# Rx.net
KiCad netlist of a schematic drawn in EAGLE
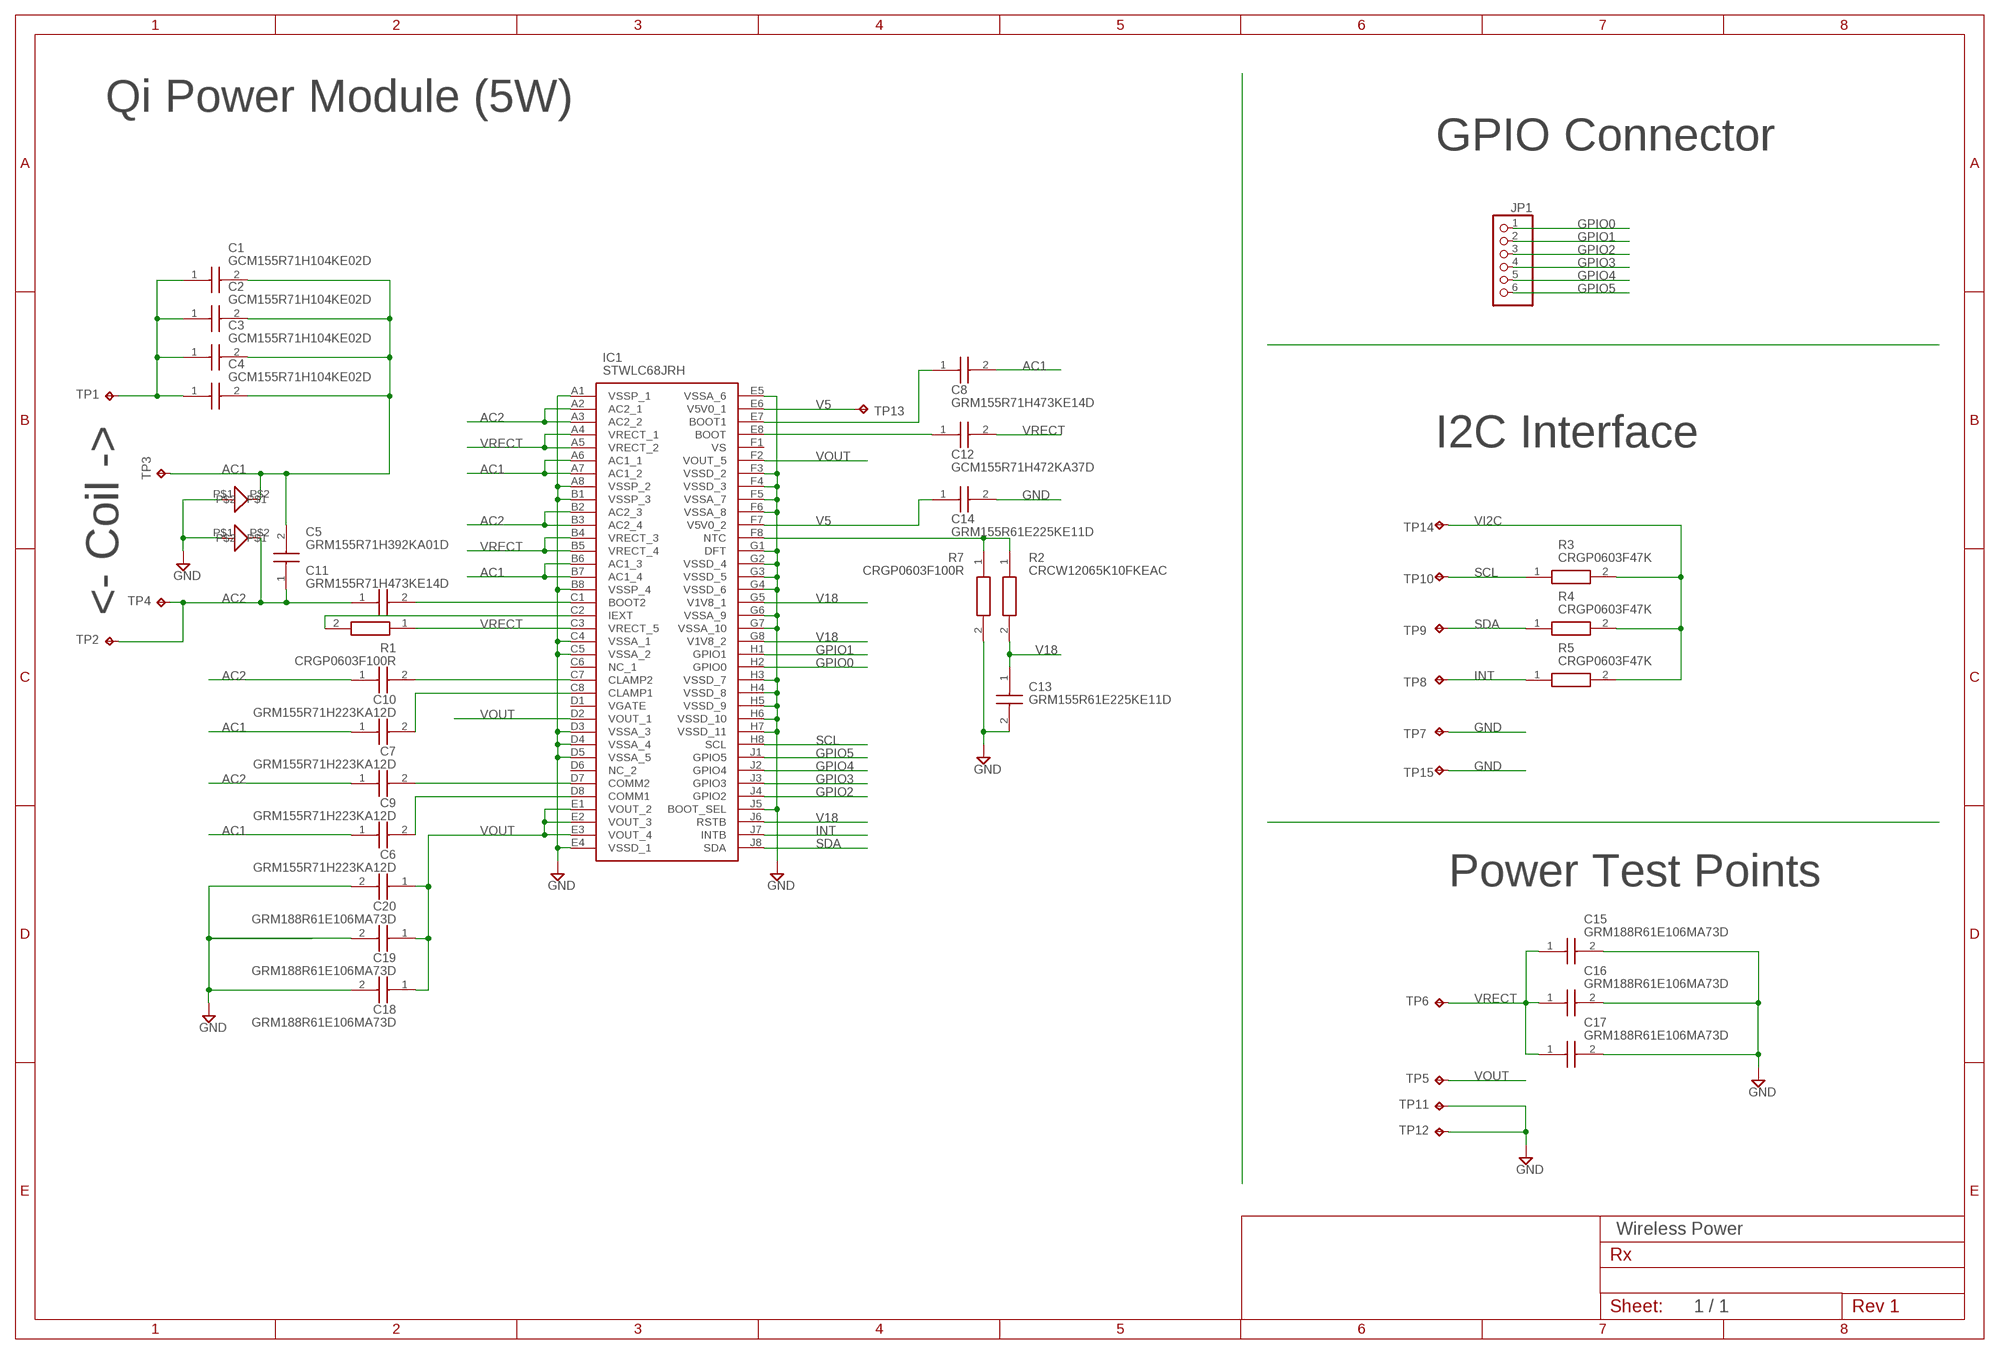
[diagram p0: schematic, sheet 1]

(export (version "E")
  (design (tool "Eeschema 10.0.6"))
  (components
    (comp (ref "C1")
      (value "GCM155R71H104KE02D")
      (footprint "eagle-import:CAPC1005X55N")
      (fields (field (name "MOUSER_PART_NUMBER") "81-GCM155R71H104KE2D"))
      (libsource (lib "eagle-import") (part "GCM155R71H104KE02D"))
    )
    (comp (ref "C2")
      (value "GCM155R71H104KE02D")
      (footprint "eagle-import:CAPC1005X55N")
      (fields (field (name "MOUSER_PART_NUMBER") "81-GCM155R71H104KE2D"))
      (libsource (lib "eagle-import") (part "GCM155R71H104KE02D"))
    )
    (comp (ref "C3")
      (value "GCM155R71H104KE02D")
      (footprint "eagle-import:CAPC1005X55N")
      (fields (field (name "MOUSER_PART_NUMBER") "81-GCM155R71H104KE2D"))
      (libsource (lib "eagle-import") (part "GCM155R71H104KE02D"))
    )
    (comp (ref "C4")
      (value "GCM155R71H104KE02D")
      (footprint "eagle-import:CAPC1005X55N")
      (fields (field (name "MOUSER_PART_NUMBER") "81-GCM155R71H104KE2D"))
      (libsource (lib "eagle-import") (part "GCM155R71H104KE02D"))
    )
    (comp (ref "C5")
      (value "GRM155R71H392KA01D")
      (footprint "eagle-import:CAPC1005X55N")
      (fields (field (name "MOUSER_PART_NUMBER") "81-GRM15R71H392KA01D"))
      (libsource (lib "eagle-import") (part "GRM155R71H392KA01D"))
    )
    (comp (ref "C6")
      (value "GRM155R71H223KA12D")
      (footprint "eagle-import:CAPC1005X55N")
      (fields (field (name "MOUSER_PART_NUMBER") "81-GRM155R71H223KA12"))
      (libsource (lib "eagle-import") (part "GRM155R71H223KA12D"))
    )
    (comp (ref "C7")
      (value "GRM155R71H223KA12D")
      (footprint "eagle-import:CAPC1005X55N")
      (fields (field (name "MOUSER_PART_NUMBER") "81-GRM155R71H223KA12"))
      (libsource (lib "eagle-import") (part "GRM155R71H223KA12D"))
    )
    (comp (ref "C8")
      (value "GRM155R71H473KE14D")
      (footprint "eagle-import:CAPC1005X55N")
      (fields (field (name "MOUSER_PART_NUMBER") "81-GRM155R71H473KE4D"))
      (libsource (lib "eagle-import") (part "GRM155R71H473KE14D"))
    )
    (comp (ref "C9")
      (value "GRM155R71H223KA12D")
      (footprint "eagle-import:CAPC1005X55N")
      (fields (field (name "MOUSER_PART_NUMBER") "81-GRM155R71H223KA12"))
      (libsource (lib "eagle-import") (part "GRM155R71H223KA12D"))
    )
    (comp (ref "C10")
      (value "GRM155R71H223KA12D")
      (footprint "eagle-import:CAPC1005X55N")
      (fields (field (name "MOUSER_PART_NUMBER") "81-GRM155R71H223KA12"))
      (libsource (lib "eagle-import") (part "GRM155R71H223KA12D"))
    )
    (comp (ref "C11")
      (value "GRM155R71H473KE14D")
      (footprint "eagle-import:CAPC1005X55N")
      (fields (field (name "MOUSER_PART_NUMBER") "81-GRM155R71H473KE4D"))
      (libsource (lib "eagle-import") (part "GRM155R71H473KE14D"))
    )
    (comp (ref "C12")
      (value "GCM155R71H472KA37D")
      (footprint "eagle-import:CAPC1005X55N")
      (fields (field (name "MOUSER_PART_NUMBER") "81-GCM155R71H472K37D"))
      (libsource (lib "eagle-import") (part "GCM155R71H472KA37D"))
    )
    (comp (ref "C13")
      (value "GRM155R61E225KE11D")
      (footprint "eagle-import:CAPC1005X55N")
      (fields (field (name "MOUSER_PART_NUMBER") "81-GRM155R61E225KE1D"))
      (libsource (lib "eagle-import") (part "GRM155R61E225KE11D"))
    )
    (comp (ref "C14")
      (value "GRM155R61E225KE11D")
      (footprint "eagle-import:CAPC1005X55N")
      (fields (field (name "MOUSER_PART_NUMBER") "81-GRM155R61E225KE1D"))
      (libsource (lib "eagle-import") (part "GRM155R61E225KE11D"))
    )
    (comp (ref "C15")
      (value "GRM188R61E106MA73D")
      (footprint "eagle-import:CAPC1608X90N")
      (fields (field (name "MOUSER_PART_NUMBER") "81-GRM188R61E106MA3D"))
      (libsource (lib "eagle-import") (part "GRM188R61E106MA73D"))
    )
    (comp (ref "C16")
      (value "GRM188R61E106MA73D")
      (footprint "eagle-import:CAPC1608X90N")
      (fields (field (name "MOUSER_PART_NUMBER") "81-GRM188R61E106MA3D"))
      (libsource (lib "eagle-import") (part "GRM188R61E106MA73D"))
    )
    (comp (ref "C17")
      (value "GRM188R61E106MA73D")
      (footprint "eagle-import:CAPC1608X90N")
      (fields (field (name "MOUSER_PART_NUMBER") "81-GRM188R61E106MA3D"))
      (libsource (lib "eagle-import") (part "GRM188R61E106MA73D"))
    )
    (comp (ref "C18")
      (value "GRM188R61E106MA73D")
      (footprint "eagle-import:CAPC1608X90N")
      (fields (field (name "MOUSER_PART_NUMBER") "81-GRM188R61E106MA3D"))
      (libsource (lib "eagle-import") (part "GRM188R61E106MA73D"))
    )
    (comp (ref "C19")
      (value "GRM188R61E106MA73D")
      (footprint "eagle-import:CAPC1608X90N")
      (fields (field (name "MOUSER_PART_NUMBER") "81-GRM188R61E106MA3D"))
      (libsource (lib "eagle-import") (part "GRM188R61E106MA73D"))
    )
    (comp (ref "C20")
      (value "GRM188R61E106MA73D")
      (footprint "eagle-import:CAPC1608X90N")
      (fields (field (name "MOUSER_PART_NUMBER") "81-GRM188R61E106MA3D"))
      (libsource (lib "eagle-import") (part "GRM188R61E106MA73D"))
    )
    (comp (ref "IC1")
      (value "STWLC68JRH")
      (footprint "eagle-import:BGA72C40P9X9_441X376X58")
      (fields (field (name "MOUSER_PART_NUMBER") "511-STWLC68JRH"))
      (libsource (lib "eagle-import") (part "STWLC68JRH"))
    )
    (comp (ref "JP1")
      (value "PINHD-1X6")
      (footprint "eagle-import:1X06")
      (libsource (lib "eagle-import") (part "PINHD-1X6"))
    )
    (comp (ref "R1")
      (value "CRGP0603F100R")
      (footprint "eagle-import:RESC1608X55N")
      (fields (field (name "MOUSER_PART_NUMBER") "279-CRGP0603F100R"))
      (libsource (lib "eagle-import") (part "CRGP0603F100R"))
    )
    (comp (ref "R2")
      (value "CRCW12065K10FKEAC")
      (footprint "eagle-import:RESC3216X60N")
      (fields (field (name "MOUSER_PART_NUMBER") "71-CRCW12065K10FKEAC"))
      (libsource (lib "eagle-import") (part "CRCW12065K10FKEAC"))
    )
    (comp (ref "R3")
      (value "CRGP0603F47K")
      (footprint "eagle-import:RESC1608X55N")
      (fields (field (name "MOUSER_PART_NUMBER") "279-CRGP0603F47K"))
      (libsource (lib "eagle-import") (part "CRGP0603F47K"))
    )
    (comp (ref "R4")
      (value "CRGP0603F47K")
      (footprint "eagle-import:RESC1608X55N")
      (fields (field (name "MOUSER_PART_NUMBER") "279-CRGP0603F47K"))
      (libsource (lib "eagle-import") (part "CRGP0603F47K"))
    )
    (comp (ref "R5")
      (value "CRGP0603F47K")
      (footprint "eagle-import:RESC1608X55N")
      (fields (field (name "MOUSER_PART_NUMBER") "279-CRGP0603F47K"))
      (libsource (lib "eagle-import") (part "CRGP0603F47K"))
    )
    (comp (ref "R7")
      (value "CRGP0603F100R")
      (footprint "eagle-import:RESC1608X55N")
      (fields (field (name "MOUSER_PART_NUMBER") "279-CRGP0603F100R"))
      (libsource (lib "eagle-import") (part "CRGP0603F100R"))
    )
    (comp (ref "TP1")
      (value "TPPAD1-13")
      (footprint "eagle-import:P1-13")
      (libsource (lib "eagle-import") (part "TPPAD1-13"))
    )
    (comp (ref "TP2")
      (value "TPPAD1-13")
      (footprint "eagle-import:P1-13")
      (libsource (lib "eagle-import") (part "TPPAD1-13"))
    )
    (comp (ref "TP3")
      (value "TPPAD1-13")
      (footprint "eagle-import:P1-13")
      (libsource (lib "eagle-import") (part "TPPAD1-13"))
    )
    (comp (ref "TP4")
      (value "TPPAD1-13")
      (footprint "eagle-import:P1-13")
      (libsource (lib "eagle-import") (part "TPPAD1-13"))
    )
    (comp (ref "TP5")
      (value "TPPAD1-13")
      (footprint "eagle-import:P1-13")
      (libsource (lib "eagle-import") (part "TPPAD1-13"))
    )
    (comp (ref "TP6")
      (value "TPPAD1-13")
      (footprint "eagle-import:P1-13")
      (libsource (lib "eagle-import") (part "TPPAD1-13"))
    )
    (comp (ref "TP7")
      (value "TPPAD1-13")
      (footprint "eagle-import:P1-13")
      (libsource (lib "eagle-import") (part "TPPAD1-13"))
    )
    (comp (ref "TP8")
      (value "TPPAD1-13")
      (footprint "eagle-import:P1-13")
      (libsource (lib "eagle-import") (part "TPPAD1-13"))
    )
    (comp (ref "TP9")
      (value "TPPAD1-13")
      (footprint "eagle-import:P1-13")
      (libsource (lib "eagle-import") (part "TPPAD1-13"))
    )
    (comp (ref "TP10")
      (value "TPPAD1-13")
      (footprint "eagle-import:P1-13")
      (libsource (lib "eagle-import") (part "TPPAD1-13"))
    )
    (comp (ref "TP11")
      (value "TPPAD1-13")
      (footprint "eagle-import:P1-13")
      (libsource (lib "eagle-import") (part "TPPAD1-13"))
    )
    (comp (ref "TP12")
      (value "TPPAD1-13")
      (footprint "eagle-import:P1-13")
      (libsource (lib "eagle-import") (part "TPPAD1-13"))
    )
    (comp (ref "TP13")
      (value "TPPAD1-13")
      (footprint "eagle-import:P1-13")
      (libsource (lib "eagle-import") (part "TPPAD1-13"))
    )
    (comp (ref "TP14")
      (value "TPPAD1-13")
      (footprint "eagle-import:P1-13")
      (libsource (lib "eagle-import") (part "TPPAD1-13"))
    )
    (comp (ref "TP15")
      (value "TPPAD1-13")
      (footprint "eagle-import:P1-13")
      (libsource (lib "eagle-import") (part "TPPAD1-13"))
    )
    (comp (ref "U$1")
      (value "SMAJ16A")
      (footprint "eagle-import:SMAJ16A")
      (libsource (lib "eagle-import") (part "SMAJ16A"))
    )
    (comp (ref "U$2")
      (value "SMAJ16A")
      (footprint "eagle-import:SMAJ16A")
      (libsource (lib "eagle-import") (part "SMAJ16A"))
    )
  )
  (nets
    (net (code "1") (name "/AC1") (class "Default")
      (node (ref "C1") (pin "2") (pinfunction "2_2") (pintype "bidirectional"))
      (node (ref "C2") (pin "2") (pinfunction "2_2") (pintype "bidirectional"))
      (node (ref "C3") (pin "2") (pinfunction "2_2") (pintype "bidirectional"))
      (node (ref "C4") (pin "2") (pinfunction "2_2") (pintype "bidirectional"))
      (node (ref "C5") (pin "2") (pinfunction "2_2") (pintype "bidirectional"))
      (node (ref "C6") (pin "1") (pinfunction "1_1") (pintype "bidirectional"))
      (node (ref "C7") (pin "1") (pinfunction "1_1") (pintype "bidirectional"))
      (node (ref "C8") (pin "2") (pinfunction "2_2") (pintype "bidirectional"))
      (node (ref "IC1") (pin "A6") (pinfunction "AC1_1_A6") (pintype "bidirectional"))
      (node (ref "IC1") (pin "A7") (pinfunction "AC1_2_A7") (pintype "bidirectional"))
      (node (ref "IC1") (pin "B6") (pinfunction "AC1_3_B6") (pintype "bidirectional"))
      (node (ref "IC1") (pin "B7") (pinfunction "AC1_4_B7") (pintype "bidirectional"))
      (node (ref "TP3") (pin "TP") (pinfunction "TP_TP") (pintype "input"))
      (node (ref "U$1") (pin "P$2") (pinfunction "P$2_P$2") (pintype "output"))
    )
    (net (code "2") (name "/AC2") (class "Default")
      (node (ref "C10") (pin "1") (pinfunction "1_1") (pintype "bidirectional"))
      (node (ref "C11") (pin "1") (pinfunction "1_1") (pintype "bidirectional"))
      (node (ref "C5") (pin "1") (pinfunction "1_1") (pintype "bidirectional"))
      (node (ref "C9") (pin "1") (pinfunction "1_1") (pintype "bidirectional"))
      (node (ref "IC1") (pin "A2") (pinfunction "AC2_1_A2") (pintype "bidirectional"))
      (node (ref "IC1") (pin "A3") (pinfunction "AC2_2_A3") (pintype "bidirectional"))
      (node (ref "IC1") (pin "B2") (pinfunction "AC2_3_B2") (pintype "bidirectional"))
      (node (ref "IC1") (pin "B3") (pinfunction "AC2_4_B3") (pintype "bidirectional"))
      (node (ref "TP2") (pin "TP") (pinfunction "TP_TP") (pintype "input"))
      (node (ref "TP4") (pin "TP") (pinfunction "TP_TP") (pintype "input"))
      (node (ref "U$2") (pin "P$2") (pinfunction "P$2_P$2") (pintype "output"))
    )
    (net (code "3") (name "/GPIO0") (class "Default")
      (node (ref "IC1") (pin "H2") (pinfunction "GPIO0_H2") (pintype "bidirectional"))
      (node (ref "JP1") (pin "1") (pinfunction "1_1") (pintype "passive"))
    )
    (net (code "4") (name "/GPIO1") (class "Default")
      (node (ref "IC1") (pin "H1") (pinfunction "GPIO1_H1") (pintype "bidirectional"))
      (node (ref "JP1") (pin "2") (pinfunction "2_2") (pintype "passive"))
    )
    (net (code "5") (name "/GPIO2") (class "Default")
      (node (ref "IC1") (pin "J4") (pinfunction "GPIO2_J4") (pintype "bidirectional"))
      (node (ref "JP1") (pin "3") (pinfunction "3_3") (pintype "passive"))
    )
    (net (code "6") (name "/GPIO3") (class "Default")
      (node (ref "IC1") (pin "J3") (pinfunction "GPIO3_J3") (pintype "bidirectional"))
      (node (ref "JP1") (pin "4") (pinfunction "4_4") (pintype "passive"))
    )
    (net (code "7") (name "/GPIO4") (class "Default")
      (node (ref "IC1") (pin "J2") (pinfunction "GPIO4_J2") (pintype "bidirectional"))
      (node (ref "JP1") (pin "5") (pinfunction "5_5") (pintype "passive"))
    )
    (net (code "8") (name "/GPIO5") (class "Default")
      (node (ref "IC1") (pin "J1") (pinfunction "GPIO5_J1") (pintype "bidirectional"))
      (node (ref "JP1") (pin "6") (pinfunction "6_6") (pintype "passive"))
    )
    (net (code "9") (name "/INT") (class "Default")
      (node (ref "IC1") (pin "J7") (pinfunction "INTB_J7") (pintype "bidirectional"))
      (node (ref "R5") (pin "1") (pinfunction "1_1") (pintype "bidirectional"))
      (node (ref "TP8") (pin "TP") (pinfunction "TP_TP") (pintype "input"))
    )
    (net (code "11") (name "/SCL") (class "Default")
      (node (ref "IC1") (pin "H8") (pinfunction "SCL_H8") (pintype "bidirectional"))
      (node (ref "R3") (pin "1") (pinfunction "1_1") (pintype "bidirectional"))
      (node (ref "TP10") (pin "TP") (pinfunction "TP_TP") (pintype "input"))
    )
    (net (code "12") (name "/SDA") (class "Default")
      (node (ref "IC1") (pin "J8") (pinfunction "SDA_J8") (pintype "bidirectional"))
      (node (ref "R4") (pin "1") (pinfunction "1_1") (pintype "bidirectional"))
      (node (ref "TP9") (pin "TP") (pinfunction "TP_TP") (pintype "input"))
    )
    (net (code "13") (name "/V5") (class "Default")
      (node (ref "C14") (pin "1") (pinfunction "1_1") (pintype "bidirectional"))
      (node (ref "IC1") (pin "E6") (pinfunction "V5V0_1_E6") (pintype "bidirectional"))
      (node (ref "IC1") (pin "F7") (pinfunction "V5V0_2_F7") (pintype "bidirectional"))
      (node (ref "TP13") (pin "TP") (pinfunction "TP_TP") (pintype "input"))
    )
    (net (code "14") (name "/V18") (class "Default")
      (node (ref "C13") (pin "1") (pinfunction "1_1") (pintype "bidirectional"))
      (node (ref "IC1") (pin "G5") (pinfunction "V1V8_1_G5") (pintype "bidirectional"))
      (node (ref "IC1") (pin "G8") (pinfunction "V1V8_2_G8") (pintype "bidirectional"))
      (node (ref "IC1") (pin "J6") (pinfunction "RSTB_J6") (pintype "bidirectional"))
      (node (ref "R2") (pin "2") (pinfunction "2_2") (pintype "bidirectional"))
    )
    (net (code "15") (name "/VI2C") (class "Default")
      (node (ref "R3") (pin "2") (pinfunction "2_2") (pintype "bidirectional"))
      (node (ref "R4") (pin "2") (pinfunction "2_2") (pintype "bidirectional"))
      (node (ref "R5") (pin "2") (pinfunction "2_2") (pintype "bidirectional"))
      (node (ref "TP14") (pin "TP") (pinfunction "TP_TP") (pintype "input"))
    )
    (net (code "16") (name "/VOUT") (class "Default")
      (node (ref "C18") (pin "1") (pinfunction "1_1") (pintype "bidirectional"))
      (node (ref "C19") (pin "1") (pinfunction "1_1") (pintype "bidirectional"))
      (node (ref "C20") (pin "1") (pinfunction "1_1") (pintype "bidirectional"))
      (node (ref "IC1") (pin "D2") (pinfunction "VOUT_1_D2") (pintype "bidirectional"))
      (node (ref "IC1") (pin "E1") (pinfunction "VOUT_2_E1") (pintype "bidirectional"))
      (node (ref "IC1") (pin "E2") (pinfunction "VOUT_3_E2") (pintype "bidirectional"))
      (node (ref "IC1") (pin "E3") (pinfunction "VOUT_4_E3") (pintype "bidirectional"))
      (node (ref "IC1") (pin "F2") (pinfunction "VOUT_5_F2") (pintype "bidirectional"))
      (node (ref "TP5") (pin "TP") (pinfunction "TP_TP") (pintype "input"))
    )
    (net (code "17") (name "/VRECT") (class "Default")
      (node (ref "C12") (pin "2") (pinfunction "2_2") (pintype "bidirectional"))
      (node (ref "C15") (pin "1") (pinfunction "1_1") (pintype "bidirectional"))
      (node (ref "C16") (pin "1") (pinfunction "1_1") (pintype "bidirectional"))
      (node (ref "C17") (pin "1") (pinfunction "1_1") (pintype "bidirectional"))
      (node (ref "IC1") (pin "A4") (pinfunction "VRECT_1_A4") (pintype "bidirectional"))
      (node (ref "IC1") (pin "A5") (pinfunction "VRECT_2_A5") (pintype "bidirectional"))
      (node (ref "IC1") (pin "B4") (pinfunction "VRECT_3_B4") (pintype "bidirectional"))
      (node (ref "IC1") (pin "B5") (pinfunction "VRECT_4_B5") (pintype "bidirectional"))
      (node (ref "IC1") (pin "C3") (pinfunction "VRECT_5_C3") (pintype "bidirectional"))
      (node (ref "R1") (pin "1") (pinfunction "1_1") (pintype "bidirectional"))
      (node (ref "TP6") (pin "TP") (pinfunction "TP_TP") (pintype "input"))
    )
    (net (code "18") (name "GND") (class "Default")
      (node (ref "C13") (pin "2") (pinfunction "2_2") (pintype "bidirectional"))
      (node (ref "C14") (pin "2") (pinfunction "2_2") (pintype "bidirectional"))
      (node (ref "C15") (pin "2") (pinfunction "2_2") (pintype "bidirectional"))
      (node (ref "C16") (pin "2") (pinfunction "2_2") (pintype "bidirectional"))
      (node (ref "C17") (pin "2") (pinfunction "2_2") (pintype "bidirectional"))
      (node (ref "C18") (pin "2") (pinfunction "2_2") (pintype "bidirectional"))
      (node (ref "C19") (pin "2") (pinfunction "2_2") (pintype "bidirectional"))
      (node (ref "C20") (pin "2") (pinfunction "2_2") (pintype "bidirectional"))
      (node (ref "IC1") (pin "A1") (pinfunction "VSSP_1_A1") (pintype "bidirectional"))
      (node (ref "IC1") (pin "A8") (pinfunction "VSSP_2_A8") (pintype "bidirectional"))
      (node (ref "IC1") (pin "B1") (pinfunction "VSSP_3_B1") (pintype "bidirectional"))
      (node (ref "IC1") (pin "B8") (pinfunction "VSSP_4_B8") (pintype "bidirectional"))
      (node (ref "IC1") (pin "C4") (pinfunction "VSSA_1_C4") (pintype "bidirectional"))
      (node (ref "IC1") (pin "C5") (pinfunction "VSSA_2_C5") (pintype "bidirectional"))
      (node (ref "IC1") (pin "D3") (pinfunction "VSSA_3_D3") (pintype "bidirectional"))
      (node (ref "IC1") (pin "D4") (pinfunction "VSSA_4_D4") (pintype "bidirectional"))
      (node (ref "IC1") (pin "D5") (pinfunction "VSSA_5_D5") (pintype "bidirectional"))
      (node (ref "IC1") (pin "E4") (pinfunction "VSSD_1_E4") (pintype "bidirectional"))
      (node (ref "IC1") (pin "E5") (pinfunction "VSSA_6_E5") (pintype "bidirectional"))
      (node (ref "IC1") (pin "F3") (pinfunction "VSSD_2_F3") (pintype "bidirectional"))
      (node (ref "IC1") (pin "F4") (pinfunction "VSSD_3_F4") (pintype "bidirectional"))
      (node (ref "IC1") (pin "F5") (pinfunction "VSSA_7_F5") (pintype "bidirectional"))
      (node (ref "IC1") (pin "F6") (pinfunction "VSSA_8_F6") (pintype "bidirectional"))
      (node (ref "IC1") (pin "G1") (pinfunction "DFT_G1") (pintype "bidirectional"))
      (node (ref "IC1") (pin "G2") (pinfunction "VSSD_4_G2") (pintype "bidirectional"))
      (node (ref "IC1") (pin "G3") (pinfunction "VSSD_5_G3") (pintype "bidirectional"))
      (node (ref "IC1") (pin "G4") (pinfunction "VSSD_6_G4") (pintype "bidirectional"))
      (node (ref "IC1") (pin "G6") (pinfunction "VSSA_9_G6") (pintype "bidirectional"))
      (node (ref "IC1") (pin "G7") (pinfunction "VSSA_10_G7") (pintype "bidirectional"))
      (node (ref "IC1") (pin "H3") (pinfunction "VSSD_7_H3") (pintype "bidirectional"))
      (node (ref "IC1") (pin "H4") (pinfunction "VSSD_8_H4") (pintype "bidirectional"))
      (node (ref "IC1") (pin "H5") (pinfunction "VSSD_9_H5") (pintype "bidirectional"))
      (node (ref "IC1") (pin "H6") (pinfunction "VSSD_10_H6") (pintype "bidirectional"))
      (node (ref "IC1") (pin "H7") (pinfunction "VSSD_11_H7") (pintype "bidirectional"))
      (node (ref "IC1") (pin "J5") (pinfunction "BOOT_SEL_J5") (pintype "bidirectional"))
      (node (ref "R7") (pin "2") (pinfunction "2_2") (pintype "bidirectional"))
      (node (ref "TP11") (pin "TP") (pinfunction "TP_TP") (pintype "input"))
      (node (ref "TP12") (pin "TP") (pinfunction "TP_TP") (pintype "input"))
      (node (ref "TP15") (pin "TP") (pinfunction "TP_TP") (pintype "input"))
      (node (ref "TP7") (pin "TP") (pinfunction "TP_TP") (pintype "input"))
      (node (ref "U$1") (pin "P$1") (pinfunction "P$1_P$1") (pintype "input"))
      (node (ref "U$2") (pin "P$1") (pinfunction "P$1_P$1") (pintype "input"))
    )
    (net (code "19") (name "Net-(C1-Pad1)") (class "Default")
      (node (ref "C1") (pin "1") (pinfunction "1_1") (pintype "bidirectional"))
      (node (ref "C2") (pin "1") (pinfunction "1_1") (pintype "bidirectional"))
      (node (ref "C3") (pin "1") (pinfunction "1_1") (pintype "bidirectional"))
      (node (ref "C4") (pin "1") (pinfunction "1_1") (pintype "bidirectional"))
      (node (ref "TP1") (pin "TP") (pinfunction "TP_TP") (pintype "input"))
    )
    (net (code "20") (name "Net-(IC1-BOOT)") (class "Default")
      (node (ref "C12") (pin "1") (pinfunction "1_1") (pintype "bidirectional"))
      (node (ref "IC1") (pin "E8") (pinfunction "BOOT_E8") (pintype "bidirectional"))
    )
    (net (code "21") (name "Net-(IC1-BOOT1)") (class "Default")
      (node (ref "C8") (pin "1") (pinfunction "1_1") (pintype "bidirectional"))
      (node (ref "IC1") (pin "E7") (pinfunction "BOOT1_E7") (pintype "bidirectional"))
    )
    (net (code "22") (name "Net-(IC1-BOOT2)") (class "Default")
      (node (ref "C11") (pin "2") (pinfunction "2_2") (pintype "bidirectional"))
      (node (ref "IC1") (pin "C1") (pinfunction "BOOT2_C1") (pintype "bidirectional"))
    )
    (net (code "23") (name "Net-(IC1-CLAMP1)") (class "Default")
      (node (ref "C7") (pin "2") (pinfunction "2_2") (pintype "bidirectional"))
      (node (ref "IC1") (pin "C8") (pinfunction "CLAMP1_C8") (pintype "bidirectional"))
    )
    (net (code "24") (name "Net-(IC1-CLAMP2)") (class "Default")
      (node (ref "C10") (pin "2") (pinfunction "2_2") (pintype "bidirectional"))
      (node (ref "IC1") (pin "C7") (pinfunction "CLAMP2_C7") (pintype "bidirectional"))
    )
    (net (code "25") (name "Net-(IC1-COMM1)") (class "Default")
      (node (ref "C6") (pin "2") (pinfunction "2_2") (pintype "bidirectional"))
      (node (ref "IC1") (pin "D8") (pinfunction "COMM1_D8") (pintype "bidirectional"))
    )
    (net (code "26") (name "Net-(IC1-COMM2)") (class "Default")
      (node (ref "C9") (pin "2") (pinfunction "2_2") (pintype "bidirectional"))
      (node (ref "IC1") (pin "D7") (pinfunction "COMM2_D7") (pintype "bidirectional"))
    )
    (net (code "27") (name "Net-(IC1-IEXT)") (class "Default")
      (node (ref "IC1") (pin "C2") (pinfunction "IEXT_C2") (pintype "bidirectional"))
      (node (ref "R1") (pin "2") (pinfunction "2_2") (pintype "bidirectional"))
    )
    (net (code "28") (name "Net-(IC1-NTC)") (class "Default")
      (node (ref "IC1") (pin "F8") (pinfunction "NTC_F8") (pintype "bidirectional"))
      (node (ref "R2") (pin "1") (pinfunction "1_1") (pintype "bidirectional"))
      (node (ref "R7") (pin "1") (pinfunction "1_1") (pintype "bidirectional"))
    )
    (net (code "29") (name "unconnected-(IC1-NC_1-PadC6)") (class "Default")
      (node (ref "IC1") (pin "C6") (pinfunction "NC_1_C6") (pintype "bidirectional"))
    )
    (net (code "30") (name "unconnected-(IC1-NC_2-PadD6)") (class "Default")
      (node (ref "IC1") (pin "D6") (pinfunction "NC_2_D6") (pintype "bidirectional"))
    )
    (net (code "31") (name "unconnected-(IC1-VGATE-PadD1)") (class "Default")
      (node (ref "IC1") (pin "D1") (pinfunction "VGATE_D1") (pintype "bidirectional"))
    )
    (net (code "32") (name "unconnected-(IC1-VS-PadF1)") (class "Default")
      (node (ref "IC1") (pin "F1") (pinfunction "VS_F1") (pintype "bidirectional"))
    )
  )
)
